# TVR_Rev2_Sensors_Actuators.net
KiCad netlist of a schematic drawn in Altium Designer
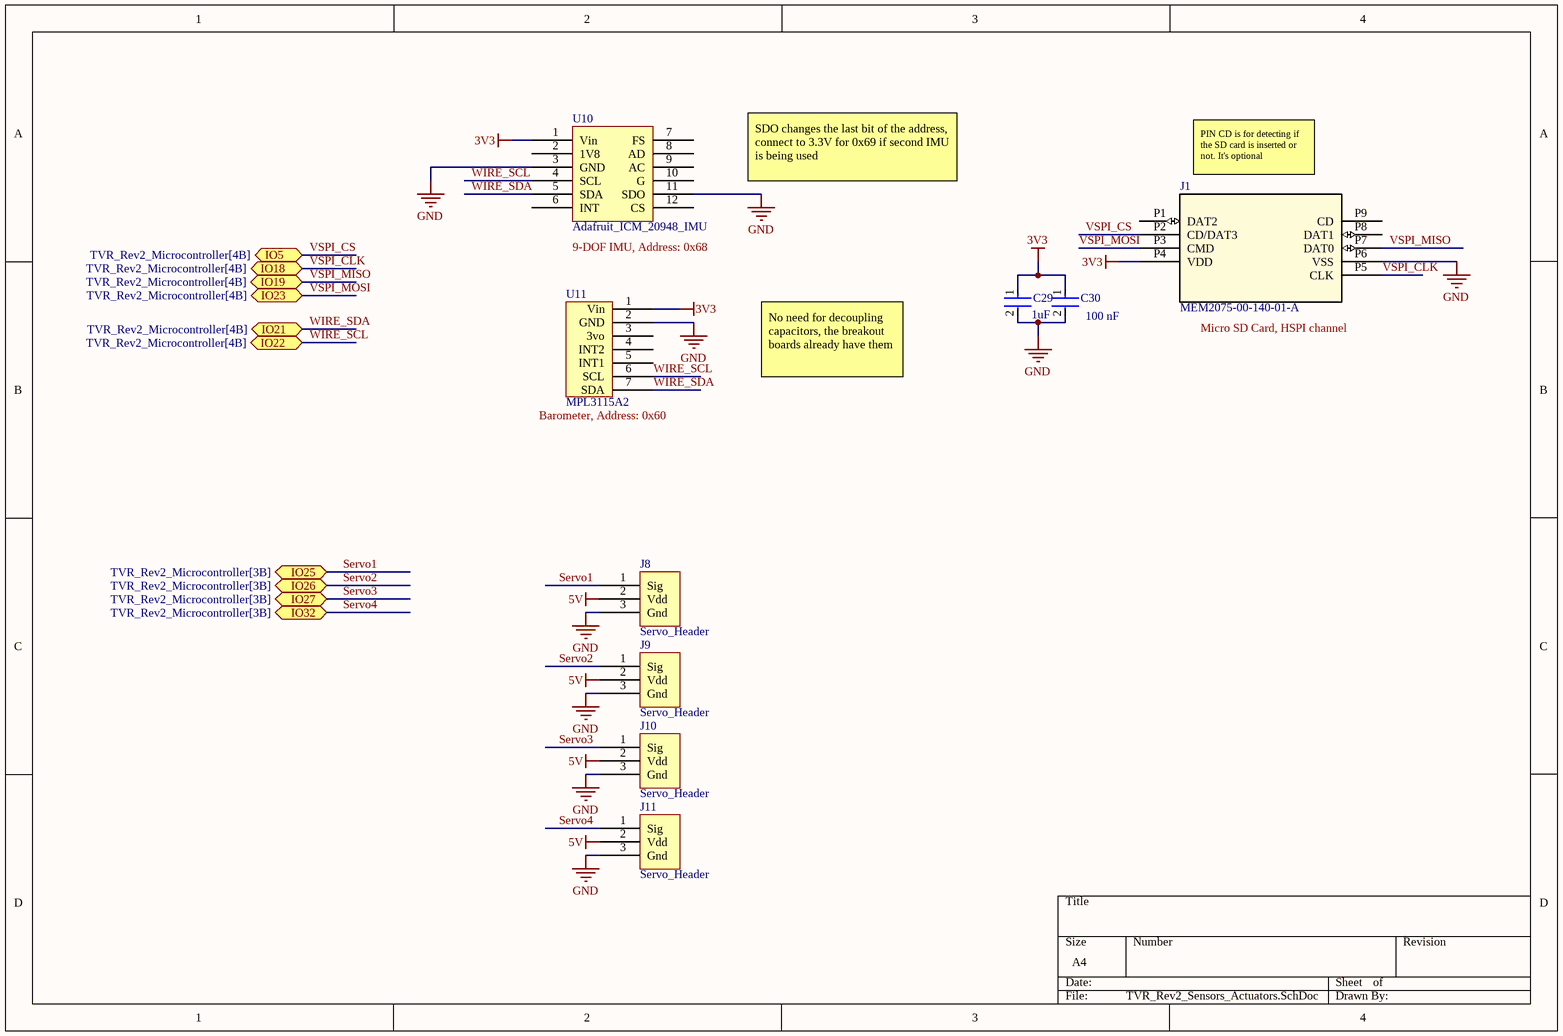
[diagram p0: TVR_Rev2_Sensors_Actuators.SchDoc]

(export (version "E")
  (design (tool "Eeschema 10.0.6"))
  (components
    (comp (ref "C29")
      (value "08055C105KAT2A")
      (footprint "FP-0805-L_2_01_0_2-W_1_25-MFG")
      (description "General Purpose Ceramic Capacitor, 0805, 1uF, 10%, X7R, 15%, 50V")
      (fields
        (field (name "TOLERANCE") "10%")
        (field (name "CAPACITANCE") "1uF")
        (field (name "VOLTAGE") "50V")
      )
      (libsource (lib "Altium Content Vault") (part "b4654b650e69147ec39a6b967a45e02"))
    )
    (comp (ref "C30")
      (value "CC0805KRX7R9BB104")
      (footprint "FP-CC0805-0_85-MFG")
      (description "CAP CER 0.1UF 50V X7R 0805")
      (fields
        (field (name "TOLERANCE") "0.1")
        (field (name "CAPACITANCE") "100 nF")
        (field (name "MANUFACTURER") "Yageo")
      )
      (libsource (lib "Altium Content Vault") (part "11868f565c42a9108669ba33697ecf6"))
    )
    (comp (ref "J1")
      (value "MEM2075-00-140-01-A")
      (footprint "MEM2075-00-140-01-A_GCT")
      (description "No Description Available")
      (libsource (lib "TVR") (part "MEM2075-00-140-01-A"))
    )
    (comp (ref "J8")
      (value "Servo_Header")
      (footprint "ServoHeader")
      (libsource (lib "Schlib2") (part "Servo_Header"))
    )
    (comp (ref "J9")
      (value "Servo_Header")
      (footprint "ServoHeader")
      (libsource (lib "Schlib2") (part "Servo_Header"))
    )
    (comp (ref "J10")
      (value "Servo_Header")
      (footprint "ServoHeader")
      (libsource (lib "Schlib2") (part "Servo_Header"))
    )
    (comp (ref "J11")
      (value "Servo_Header")
      (footprint "ServoHeader")
      (libsource (lib "Schlib2") (part "Servo_Header"))
    )
    (comp (ref "U10")
      (value "Adafruit_ICM_20948_IMU")
      (footprint "Adafruit_ICM_20948_IMU")
      (libsource (lib "Schlib2") (part "Adafruit_ICM_20948_IMU"))
    )
    (comp (ref "U11")
      (value "MPL3115A2")
      (footprint "MPL3115A2_DIP")
      (libsource (lib "Schlib2") (part "MPL3115A2"))
    )
  )
  (nets
    (net (code "3") (name "/Servo1") (class "Default")
      (node (ref "J8") (pin "1") (pinfunction "Sig_1") (pintype "passive"))
    )
    (net (code "4") (name "/Servo2") (class "Default")
      (node (ref "J9") (pin "1") (pinfunction "Sig_1") (pintype "passive"))
    )
    (net (code "5") (name "/Servo3") (class "Default")
      (node (ref "J10") (pin "1") (pinfunction "Sig_1") (pintype "passive"))
    )
    (net (code "6") (name "/Servo4") (class "Default")
      (node (ref "J11") (pin "1") (pinfunction "Sig_1") (pintype "passive"))
    )
    (net (code "7") (name "/VSPI_CLK") (class "Default")
      (node (ref "J1") (pin "P5") (pinfunction "CLK_P5") (pintype "passive"))
    )
    (net (code "8") (name "/VSPI_CS") (class "Default")
      (node (ref "J1") (pin "P2") (pinfunction "CD/DAT3_P2") (pintype "passive"))
    )
    (net (code "9") (name "/VSPI_MISO") (class "Default")
      (node (ref "J1") (pin "P7") (pinfunction "DAT0_P7") (pintype "bidirectional"))
    )
    (net (code "10") (name "/VSPI_MOSI") (class "Default")
      (node (ref "J1") (pin "P3") (pinfunction "CMD_P3") (pintype "passive"))
    )
    (net (code "11") (name "/WIRE_SCL") (class "Default")
      (node (ref "U10") (pin "4") (pinfunction "SCL_4") (pintype "passive"))
      (node (ref "U11") (pin "6") (pinfunction "SCL_6") (pintype "passive"))
    )
    (net (code "12") (name "/WIRE_SDA") (class "Default")
      (node (ref "U10") (pin "5") (pinfunction "SDA_5") (pintype "passive"))
      (node (ref "U11") (pin "7") (pinfunction "SDA_7") (pintype "passive"))
    )
    (net (code "13") (name "3V3") (class "Default")
      (node (ref "C29") (pin "1") (pinfunction "1_1") (pintype "passive"))
      (node (ref "C30") (pin "1") (pinfunction "1_1") (pintype "passive"))
      (node (ref "J1") (pin "P4") (pinfunction "VDD_P4") (pintype "power_in"))
      (node (ref "U10") (pin "1") (pinfunction "Vin_1") (pintype "passive"))
      (node (ref "U11") (pin "1") (pinfunction "Vin_1") (pintype "passive"))
    )
    (net (code "14") (name "5V") (class "Default")
      (node (ref "J10") (pin "2") (pinfunction "Vdd_2") (pintype "passive"))
      (node (ref "J11") (pin "2") (pinfunction "Vdd_2") (pintype "passive"))
      (node (ref "J8") (pin "2") (pinfunction "Vdd_2") (pintype "passive"))
      (node (ref "J9") (pin "2") (pinfunction "Vdd_2") (pintype "passive"))
    )
    (net (code "15") (name "GND") (class "Default")
      (node (ref "C29") (pin "2") (pinfunction "2_2") (pintype "passive"))
      (node (ref "C30") (pin "2") (pinfunction "2_2") (pintype "passive"))
      (node (ref "J1") (pin "P6") (pinfunction "VSS_P6") (pintype "power_in"))
      (node (ref "J10") (pin "3") (pinfunction "Gnd_3") (pintype "passive"))
      (node (ref "J11") (pin "3") (pinfunction "Gnd_3") (pintype "passive"))
      (node (ref "J8") (pin "3") (pinfunction "Gnd_3") (pintype "passive"))
      (node (ref "J9") (pin "3") (pinfunction "Gnd_3") (pintype "passive"))
      (node (ref "U10") (pin "11") (pinfunction "SDO_11") (pintype "passive"))
      (node (ref "U10") (pin "3") (pinfunction "GND_3") (pintype "passive"))
      (node (ref "U11") (pin "2") (pinfunction "GND_2") (pintype "passive"))
    )
    (net (code "16") (name "unconnected-(J1-CD-PadP9)") (class "Default")
      (node (ref "J1") (pin "P9") (pinfunction "CD_P9") (pintype "passive"))
    )
    (net (code "17") (name "unconnected-(J1-DAT1-PadP8)") (class "Default")
      (node (ref "J1") (pin "P8") (pinfunction "DAT1_P8") (pintype "bidirectional"))
    )
    (net (code "18") (name "unconnected-(J1-DAT2-PadP1)") (class "Default")
      (node (ref "J1") (pin "P1") (pinfunction "DAT2_P1") (pintype "bidirectional"))
    )
    (net (code "19") (name "unconnected-(U10-1V8-Pad2)") (class "Default")
      (node (ref "U10") (pin "2") (pinfunction "1V8_2") (pintype "passive"))
    )
    (net (code "20") (name "unconnected-(U10-AC-Pad9)") (class "Default")
      (node (ref "U10") (pin "9") (pinfunction "AC_9") (pintype "passive"))
    )
    (net (code "21") (name "unconnected-(U10-AD-Pad8)") (class "Default")
      (node (ref "U10") (pin "8") (pinfunction "AD_8") (pintype "passive"))
    )
    (net (code "22") (name "unconnected-(U10-CS-Pad12)") (class "Default")
      (node (ref "U10") (pin "12") (pinfunction "CS_12") (pintype "passive"))
    )
    (net (code "23") (name "unconnected-(U10-FS-Pad7)") (class "Default")
      (node (ref "U10") (pin "7") (pinfunction "FS_7") (pintype "passive"))
    )
    (net (code "24") (name "unconnected-(U10-G-Pad10)") (class "Default")
      (node (ref "U10") (pin "10") (pinfunction "G_10") (pintype "passive"))
    )
    (net (code "25") (name "unconnected-(U10-INT-Pad6)") (class "Default")
      (node (ref "U10") (pin "6") (pinfunction "INT_6") (pintype "passive"))
    )
    (net (code "26") (name "unconnected-(U11-3vo-Pad3)") (class "Default")
      (node (ref "U11") (pin "3") (pinfunction "3vo_3") (pintype "passive"))
    )
    (net (code "27") (name "unconnected-(U11-INT1-Pad5)") (class "Default")
      (node (ref "U11") (pin "5") (pinfunction "INT1_5") (pintype "passive"))
    )
    (net (code "28") (name "unconnected-(U11-INT2-Pad4)") (class "Default")
      (node (ref "U11") (pin "4") (pinfunction "INT2_4") (pintype "passive"))
    )
  )
)
